# js-wl-msp430.net
KiCad netlist of a schematic drawn in EAGLE
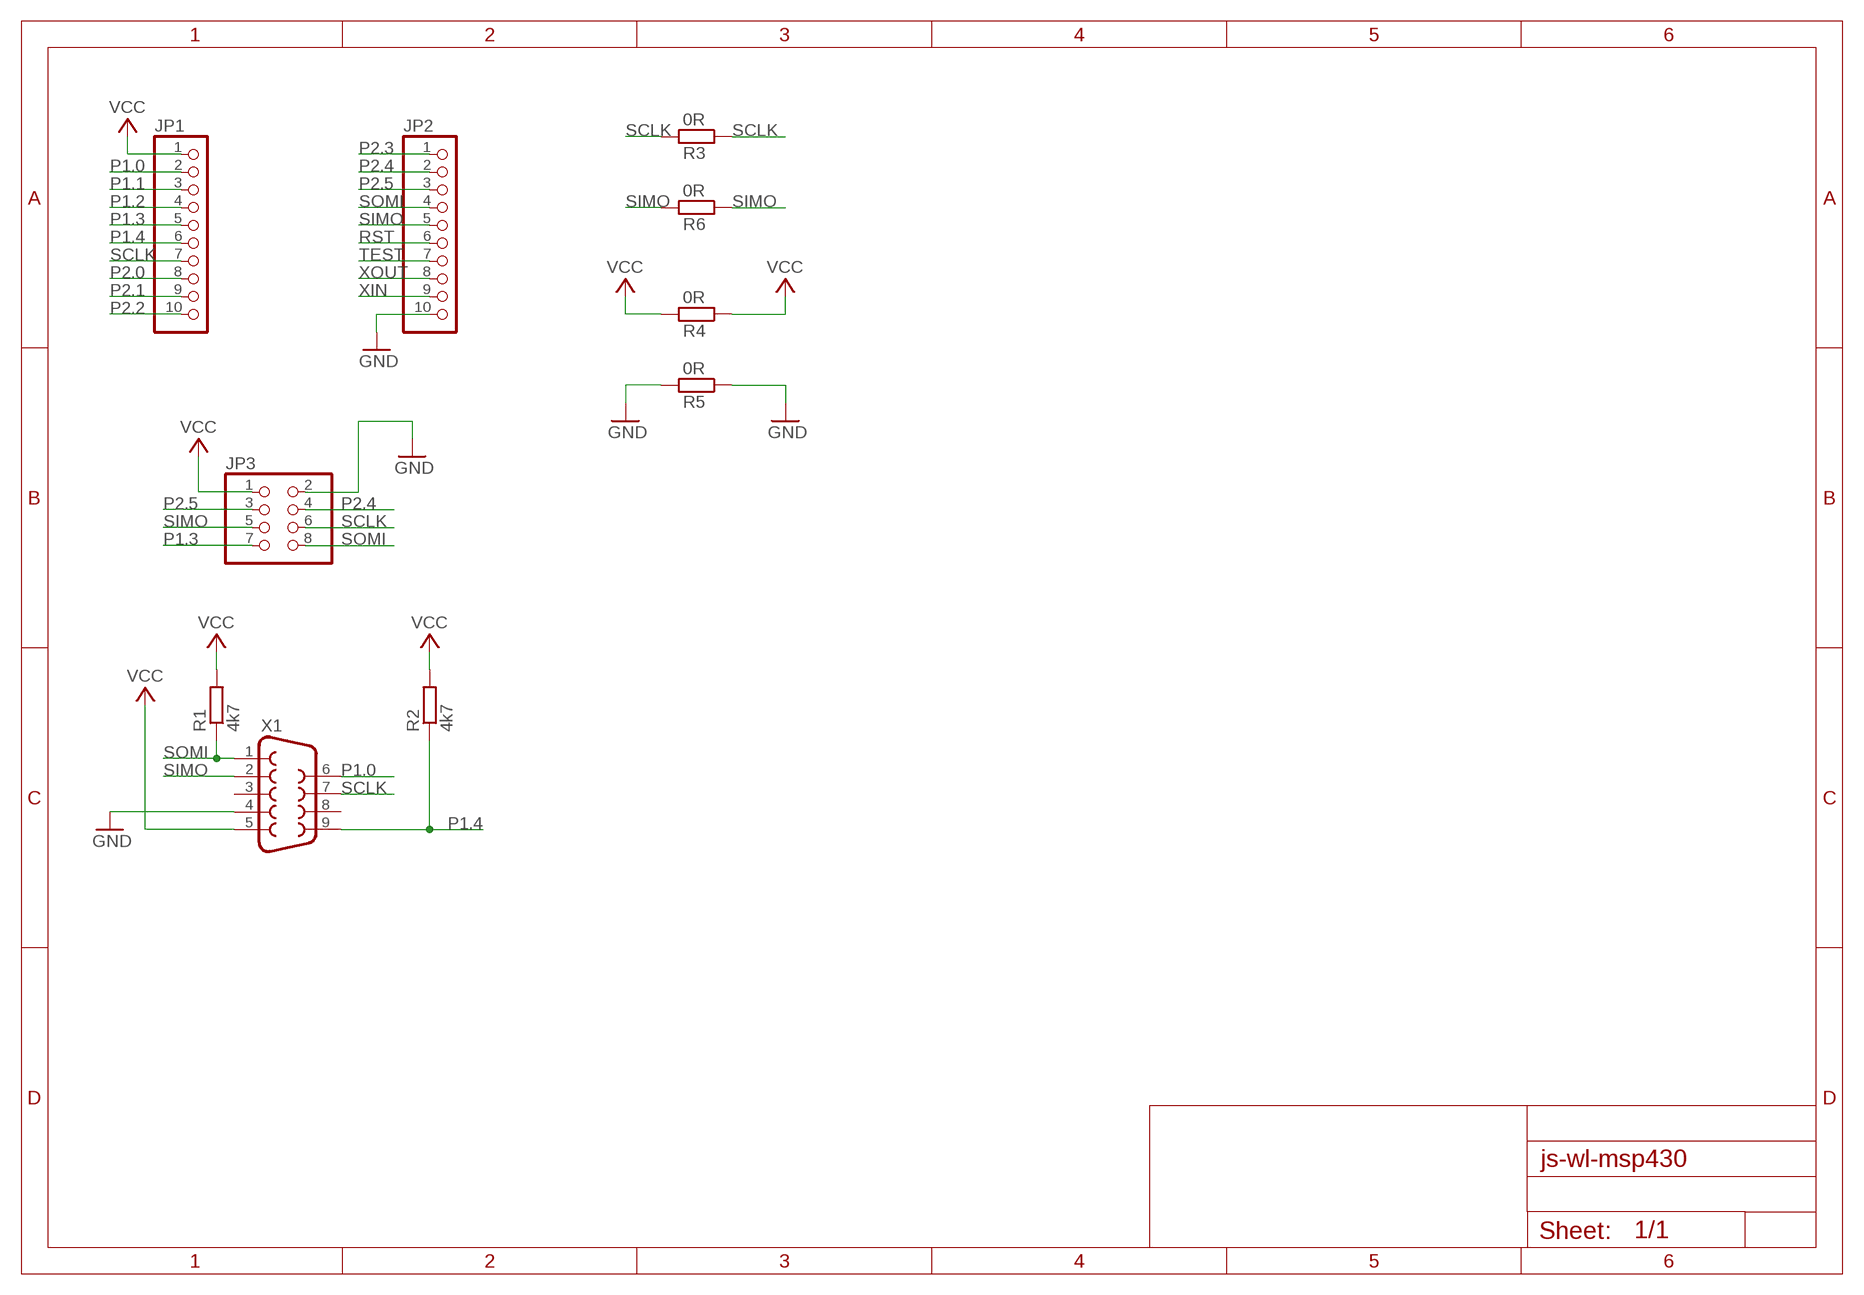
[diagram p0: schematic, sheet 1]

(export (version "E")
  (design (tool "Eeschema 10.0.6"))
  (components
    (comp (ref "JP1")
      (value "PINHD-1X10")
      (footprint "eagle-import:1X10")
      (libsource (lib "eagle-import") (part "PINHD-1X10"))
    )
    (comp (ref "JP2")
      (value "PINHD-1X10")
      (footprint "eagle-import:1X10")
      (libsource (lib "eagle-import") (part "PINHD-1X10"))
    )
    (comp (ref "JP3")
      (value "PINHD-2X4")
      (footprint "eagle-import:2X04")
      (libsource (lib "eagle-import") (part "PINHD-2X4"))
    )
    (comp (ref "R1")
      (value "4k7")
      (footprint "eagle-import:R1206")
      (libsource (lib "eagle-import") (part "R-EU_R1206"))
    )
    (comp (ref "R2")
      (value "4k7")
      (footprint "eagle-import:R1206")
      (libsource (lib "eagle-import") (part "R-EU_R1206"))
    )
    (comp (ref "R3")
      (value "0R")
      (footprint "eagle-import:R1206")
      (libsource (lib "eagle-import") (part "R-EU_R1206"))
    )
    (comp (ref "R4")
      (value "0R")
      (footprint "eagle-import:0207_12")
      (libsource (lib "eagle-import") (part "R-EU_0207/12"))
    )
    (comp (ref "R5")
      (value "0R")
      (footprint "eagle-import:0207_12")
      (libsource (lib "eagle-import") (part "R-EU_0207/12"))
    )
    (comp (ref "R6")
      (value "0R")
      (footprint "eagle-import:0207_12")
      (libsource (lib "eagle-import") (part "R-EU_0207/12"))
    )
    (comp (ref "X1")
      (value "DB9MALE")
      (footprint "eagle-import:DB9_MALE")
      (libsource (lib "eagle-import") (part "DB9MALE"))
    )
  )
  (nets
    (net (code "1") (name "/P1.0") (class "Default")
      (node (ref "JP1") (pin "2") (pinfunction "2_2") (pintype "passive"))
      (node (ref "X1") (pin "6") (pinfunction "6_6") (pintype "passive"))
    )
    (net (code "2") (name "/P1.1") (class "Default")
      (node (ref "JP1") (pin "3") (pinfunction "3_3") (pintype "passive"))
    )
    (net (code "3") (name "/P1.2") (class "Default")
      (node (ref "JP1") (pin "4") (pinfunction "4_4") (pintype "passive"))
    )
    (net (code "4") (name "/P1.3") (class "Default")
      (node (ref "JP1") (pin "5") (pinfunction "5_5") (pintype "passive"))
      (node (ref "JP3") (pin "7") (pinfunction "7_7") (pintype "passive"))
    )
    (net (code "5") (name "/P1.4") (class "Default")
      (node (ref "JP1") (pin "6") (pinfunction "6_6") (pintype "passive"))
      (node (ref "R2") (pin "1") (pinfunction "1_1") (pintype "passive"))
      (node (ref "X1") (pin "9") (pinfunction "9_9") (pintype "passive"))
    )
    (net (code "6") (name "/P2.0") (class "Default")
      (node (ref "JP1") (pin "8") (pinfunction "8_8") (pintype "passive"))
    )
    (net (code "7") (name "/P2.1") (class "Default")
      (node (ref "JP1") (pin "9") (pinfunction "9_9") (pintype "passive"))
    )
    (net (code "8") (name "/P2.2") (class "Default")
      (node (ref "JP1") (pin "10") (pinfunction "10_10") (pintype "passive"))
    )
    (net (code "9") (name "/P2.3") (class "Default")
      (node (ref "JP2") (pin "1") (pinfunction "1_1") (pintype "passive"))
    )
    (net (code "10") (name "/P2.4") (class "Default")
      (node (ref "JP2") (pin "2") (pinfunction "2_2") (pintype "passive"))
      (node (ref "JP3") (pin "4") (pinfunction "4_4") (pintype "passive"))
    )
    (net (code "11") (name "/P2.5") (class "Default")
      (node (ref "JP2") (pin "3") (pinfunction "3_3") (pintype "passive"))
      (node (ref "JP3") (pin "3") (pinfunction "3_3") (pintype "passive"))
    )
    (net (code "12") (name "/RST") (class "Default")
      (node (ref "JP2") (pin "6") (pinfunction "6_6") (pintype "passive"))
    )
    (net (code "13") (name "/SCLK") (class "Default")
      (node (ref "JP1") (pin "7") (pinfunction "7_7") (pintype "passive"))
      (node (ref "JP3") (pin "6") (pinfunction "6_6") (pintype "passive"))
      (node (ref "R3") (pin "1") (pinfunction "1_1") (pintype "passive"))
      (node (ref "R3") (pin "2") (pinfunction "2_2") (pintype "passive"))
      (node (ref "X1") (pin "7") (pinfunction "7_7") (pintype "passive"))
    )
    (net (code "14") (name "/SIMO") (class "Default")
      (node (ref "JP2") (pin "5") (pinfunction "5_5") (pintype "passive"))
      (node (ref "JP3") (pin "5") (pinfunction "5_5") (pintype "passive"))
      (node (ref "R6") (pin "1") (pinfunction "1_1") (pintype "passive"))
      (node (ref "R6") (pin "2") (pinfunction "2_2") (pintype "passive"))
      (node (ref "X1") (pin "2") (pinfunction "2_2") (pintype "passive"))
    )
    (net (code "15") (name "/SOMI") (class "Default")
      (node (ref "JP2") (pin "4") (pinfunction "4_4") (pintype "passive"))
      (node (ref "JP3") (pin "8") (pinfunction "8_8") (pintype "passive"))
      (node (ref "R1") (pin "1") (pinfunction "1_1") (pintype "passive"))
      (node (ref "X1") (pin "1") (pinfunction "1_1") (pintype "passive"))
    )
    (net (code "16") (name "/TEST") (class "Default")
      (node (ref "JP2") (pin "7") (pinfunction "7_7") (pintype "passive"))
    )
    (net (code "17") (name "/XIN") (class "Default")
      (node (ref "JP2") (pin "9") (pinfunction "9_9") (pintype "passive"))
    )
    (net (code "18") (name "/XOUT") (class "Default")
      (node (ref "JP2") (pin "8") (pinfunction "8_8") (pintype "passive"))
    )
    (net (code "19") (name "GND") (class "Default")
      (node (ref "JP2") (pin "10") (pinfunction "10_10") (pintype "passive"))
      (node (ref "JP3") (pin "2") (pinfunction "2_2") (pintype "passive"))
      (node (ref "R5") (pin "1") (pinfunction "1_1") (pintype "passive"))
      (node (ref "R5") (pin "2") (pinfunction "2_2") (pintype "passive"))
      (node (ref "X1") (pin "4") (pinfunction "4_4") (pintype "passive"))
    )
    (net (code "20") (name "VCC") (class "Default")
      (node (ref "JP1") (pin "1") (pinfunction "1_1") (pintype "passive"))
      (node (ref "JP3") (pin "1") (pinfunction "1_1") (pintype "passive"))
      (node (ref "R1") (pin "2") (pinfunction "2_2") (pintype "passive"))
      (node (ref "R2") (pin "2") (pinfunction "2_2") (pintype "passive"))
      (node (ref "R4") (pin "1") (pinfunction "1_1") (pintype "passive"))
      (node (ref "R4") (pin "2") (pinfunction "2_2") (pintype "passive"))
      (node (ref "X1") (pin "5") (pinfunction "5_5") (pintype "passive"))
    )
    (net (code "21") (name "unconnected-(X1-Pad3)") (class "Default")
      (node (ref "X1") (pin "3") (pinfunction "3_3") (pintype "passive"))
    )
    (net (code "22") (name "unconnected-(X1-Pad8)") (class "Default")
      (node (ref "X1") (pin "8") (pinfunction "8_8") (pintype "passive"))
    )
  )
)
